# uwb.net
KiCad netlist of a schematic drawn in EAGLE
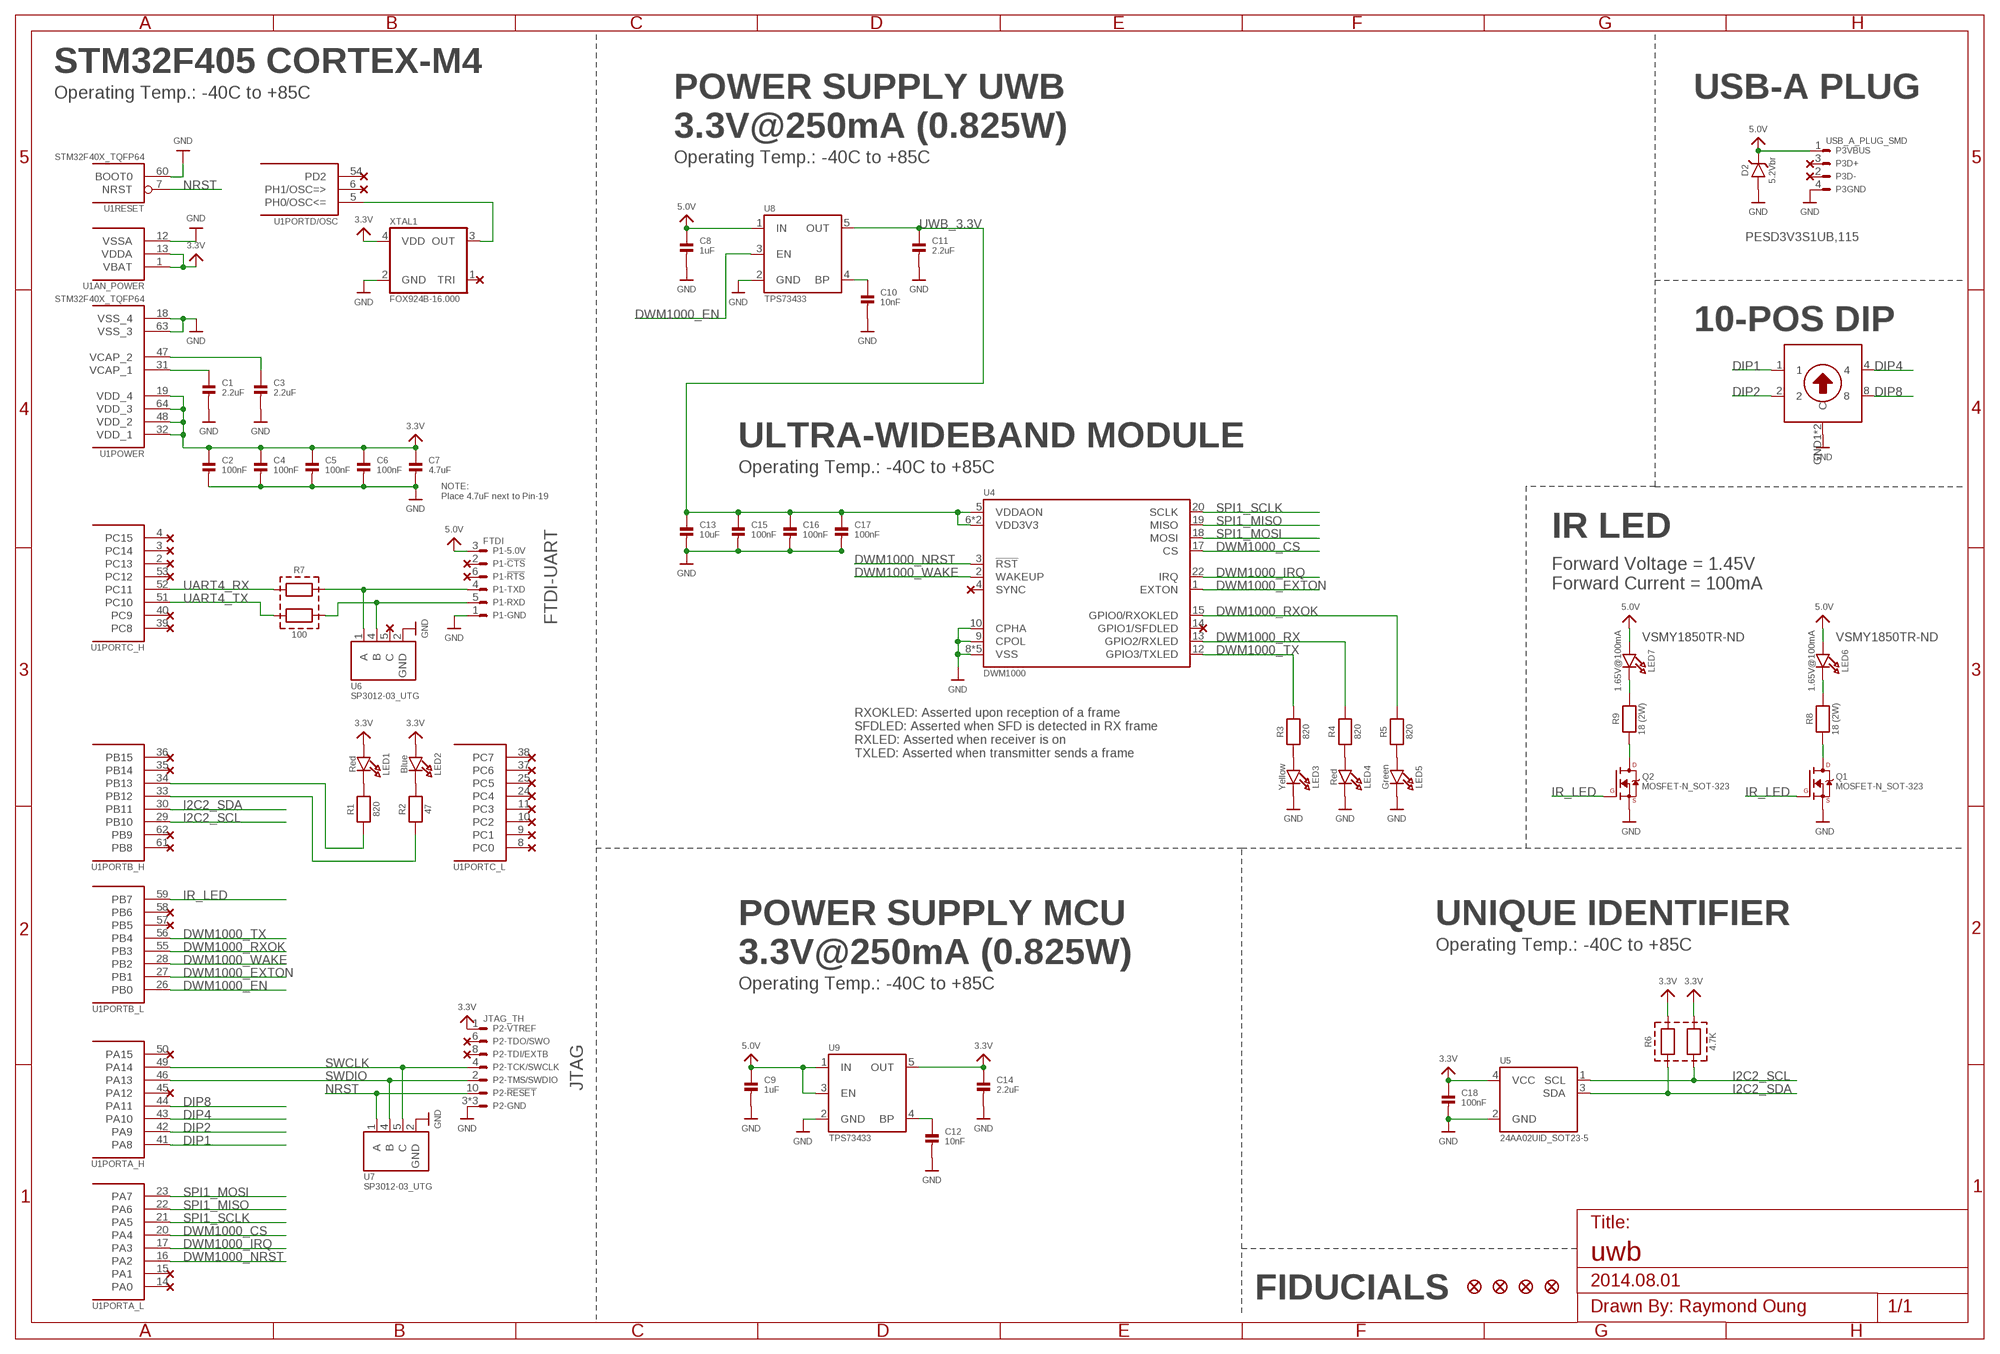
[diagram p0: schematic, sheet 1]

(export (version "E")
  (design (tool "Eeschema 10.0.6"))
  (components
    (comp (ref "C1")
      (value "2.2uF")
      (footprint "eagle-import:0402")
      (libsource (lib "eagle-import") (part "CAP_CERAMIC0402"))
    )
    (comp (ref "C2")
      (value "100nF")
      (footprint "eagle-import:0402")
      (libsource (lib "eagle-import") (part "CAP_CERAMIC0402"))
    )
    (comp (ref "C3")
      (value "2.2uF")
      (footprint "eagle-import:0402")
      (libsource (lib "eagle-import") (part "CAP_CERAMIC0402"))
    )
    (comp (ref "C4")
      (value "100nF")
      (footprint "eagle-import:0402")
      (libsource (lib "eagle-import") (part "CAP_CERAMIC0402"))
    )
    (comp (ref "C5")
      (value "100nF")
      (footprint "eagle-import:0402")
      (libsource (lib "eagle-import") (part "CAP_CERAMIC0402"))
    )
    (comp (ref "C6")
      (value "100nF")
      (footprint "eagle-import:0402")
      (libsource (lib "eagle-import") (part "CAP_CERAMIC0402"))
    )
    (comp (ref "C7")
      (value "4.7uF")
      (footprint "eagle-import:0402")
      (libsource (lib "eagle-import") (part "CAP_CERAMIC0402"))
    )
    (comp (ref "C8")
      (value "1uF")
      (footprint "eagle-import:0402")
      (libsource (lib "eagle-import") (part "CAP_CERAMIC0402"))
    )
    (comp (ref "C9")
      (value "1uF")
      (footprint "eagle-import:0402")
      (libsource (lib "eagle-import") (part "CAP_CERAMIC0402"))
    )
    (comp (ref "C10")
      (value "10nF")
      (footprint "eagle-import:0402")
      (libsource (lib "eagle-import") (part "CAP_CERAMIC0402"))
    )
    (comp (ref "C11")
      (value "2.2uF")
      (footprint "eagle-import:0402")
      (libsource (lib "eagle-import") (part "CAP_CERAMIC0402"))
    )
    (comp (ref "C12")
      (value "10nF")
      (footprint "eagle-import:0402")
      (libsource (lib "eagle-import") (part "CAP_CERAMIC0402"))
    )
    (comp (ref "C13")
      (value "10uF")
      (footprint "eagle-import:0603")
      (libsource (lib "eagle-import") (part "CAP_CERAMIC0603"))
    )
    (comp (ref "C14")
      (value "2.2uF")
      (footprint "eagle-import:0402")
      (libsource (lib "eagle-import") (part "CAP_CERAMIC0402"))
    )
    (comp (ref "C15")
      (value "100nF")
      (footprint "eagle-import:0402")
      (libsource (lib "eagle-import") (part "CAP_CERAMIC0402"))
    )
    (comp (ref "C16")
      (value "100nF")
      (footprint "eagle-import:0402")
      (libsource (lib "eagle-import") (part "CAP_CERAMIC0402"))
    )
    (comp (ref "C17")
      (value "100nF")
      (footprint "eagle-import:0402")
      (libsource (lib "eagle-import") (part "CAP_CERAMIC0402"))
    )
    (comp (ref "C18")
      (value "100nF")
      (footprint "eagle-import:0402")
      (libsource (lib "eagle-import") (part "CAP_CERAMIC0402"))
    )
    (comp (ref "D2")
      (value "5.2Vbr")
      (footprint "eagle-import:SOD-523")
      (libsource (lib "eagle-import") (part "DIODE_ZENER_SOD523"))
    )
    (comp (ref "LED1")
      (value "Red")
      (footprint "eagle-import:CHIPLED_0603")
      (libsource (lib "eagle-import") (part "LED_0603"))
    )
    (comp (ref "LED2")
      (value "Blue")
      (footprint "eagle-import:CHIPLED_0603")
      (libsource (lib "eagle-import") (part "LED_0603"))
    )
    (comp (ref "LED3")
      (value "Yellow")
      (footprint "eagle-import:CHIPLED_0603")
      (libsource (lib "eagle-import") (part "LED_0603"))
    )
    (comp (ref "LED4")
      (value "Red")
      (footprint "eagle-import:CHIPLED_0603")
      (libsource (lib "eagle-import") (part "LED_0603"))
    )
    (comp (ref "LED5")
      (value "Green")
      (footprint "eagle-import:CHIPLED_0603")
      (libsource (lib "eagle-import") (part "LED_0603"))
    )
    (comp (ref "LED6")
      (value "1.65V@100mA")
      (footprint "eagle-import:CHIPLED_0805")
      (libsource (lib "eagle-import") (part "LED_0805"))
    )
    (comp (ref "LED7")
      (value "1.65V@100mA")
      (footprint "eagle-import:CHIPLED_0805")
      (libsource (lib "eagle-import") (part "LED_0805"))
    )
    (comp (ref "P1")
      (value "FTDI")
      (footprint "eagle-import:1X06_LOCK")
      (libsource (lib "eagle-import") (part "FTDI"))
    )
    (comp (ref "P2")
      (value "JTAG_TH")
      (footprint "eagle-import:FTSH-105-01-XXX-DV")
      (libsource (lib "eagle-import") (part "JTAG_TH"))
    )
    (comp (ref "P3")
      (value "USB_A_PLUG_SMD")
      (footprint "eagle-import:USB-A_SMD")
      (libsource (lib "eagle-import") (part "USB_A_PLUG_SMD"))
    )
    (comp (ref "P4")
      (value "DIP10_SH-7000B")
      (footprint "eagle-import:SH-7000B")
      (libsource (lib "eagle-import") (part "DIP10_SH-7000B"))
    )
    (comp (ref "Q1")
      (value "MOSFET-N_SOT-323")
      (footprint "eagle-import:SOT323")
      (libsource (lib "eagle-import") (part "MOSFET-N_SOT-323"))
    )
    (comp (ref "Q2")
      (value "MOSFET-N_SOT-323")
      (footprint "eagle-import:SOT323")
      (libsource (lib "eagle-import") (part "MOSFET-N_SOT-323"))
    )
    (comp (ref "R1")
      (value "820")
      (footprint "eagle-import:0402")
      (libsource (lib "eagle-import") (part "RESISTOR0402"))
    )
    (comp (ref "R2")
      (value "47")
      (footprint "eagle-import:0402")
      (libsource (lib "eagle-import") (part "RESISTOR0402"))
    )
    (comp (ref "R3")
      (value "820")
      (footprint "eagle-import:0402")
      (libsource (lib "eagle-import") (part "RESISTOR0402"))
    )
    (comp (ref "R4")
      (value "820")
      (footprint "eagle-import:0402")
      (libsource (lib "eagle-import") (part "RESISTOR0402"))
    )
    (comp (ref "R5")
      (value "820")
      (footprint "eagle-import:0402")
      (libsource (lib "eagle-import") (part "RESISTOR0402"))
    )
    (comp (ref "R6")
      (value "4.7K")
      (footprint "eagle-import:EXBV4V")
      (libsource (lib "eagle-import") (part "RESISTOR2_0603X2"))
    )
    (comp (ref "R7")
      (value "100")
      (footprint "eagle-import:EXBV4V")
      (libsource (lib "eagle-import") (part "RESISTOR2_0603X2"))
    )
    (comp (ref "R8")
      (value "18 (2W)")
      (footprint "eagle-import:2512")
      (libsource (lib "eagle-import") (part "RESISTOR2512"))
    )
    (comp (ref "R9")
      (value "18 (2W)")
      (footprint "eagle-import:2512")
      (libsource (lib "eagle-import") (part "RESISTOR2512"))
    )
    (comp (ref "REF1")
      (value "FIDUCIAL1X2.5")
      (footprint "eagle-import:POINT-1MM")
      (libsource (lib "eagle-import") (part "FIDUCIAL1X2.5"))
    )
    (comp (ref "REF2")
      (value "FIDUCIAL1X2.5")
      (footprint "eagle-import:POINT-1MM")
      (libsource (lib "eagle-import") (part "FIDUCIAL1X2.5"))
    )
    (comp (ref "REF3")
      (value "FIDUCIAL1X2.5")
      (footprint "eagle-import:POINT-1MM")
      (libsource (lib "eagle-import") (part "FIDUCIAL1X2.5"))
    )
    (comp (ref "REF4")
      (value "FIDUCIAL1X2.5")
      (footprint "eagle-import:POINT-1MM")
      (libsource (lib "eagle-import") (part "FIDUCIAL1X2.5"))
    )
    (comp (ref "U1")
      (value "STM32F40X_TQFP64")
      (footprint "eagle-import:TQFP64")
      (libsource (lib "eagle-import") (part "STM32F40X_TQFP64"))
    )
    (comp (ref "U4")
      (value "DWM1000")
      (footprint "eagle-import:DWM1000")
      (libsource (lib "eagle-import") (part "DWM1000"))
    )
    (comp (ref "U5")
      (value "24AA02UID_SOT23-5")
      (footprint "eagle-import:SOT23-5")
      (libsource (lib "eagle-import") (part "24AA02UID_SOT23-5"))
    )
    (comp (ref "U6")
      (value "SP3012-03_UTG")
      (footprint "eagle-import:UDFN06")
      (libsource (lib "eagle-import") (part "SP3012-03_UTG"))
    )
    (comp (ref "U7")
      (value "SP3012-03_UTG")
      (footprint "eagle-import:UDFN06")
      (libsource (lib "eagle-import") (part "SP3012-03_UTG"))
    )
    (comp (ref "U8")
      (value "TPS73433")
      (footprint "eagle-import:SOT23-5")
      (libsource (lib "eagle-import") (part "TPS73433"))
    )
    (comp (ref "U9")
      (value "TPS73433")
      (footprint "eagle-import:SOT23-5")
      (libsource (lib "eagle-import") (part "TPS73433"))
    )
    (comp (ref "XTAL1")
      (value "FOX924B-16.000")
      (footprint "eagle-import:OSCILLATOR-5.0X3.2A")
      (libsource (lib "eagle-import") (part "TCXO_5.0X3.2A"))
    )
  )
  (nets
    (net (code "1") (name "/DIP1") (class "Default")
      (node (ref "P4") (pin "1") (pinfunction "1_1") (pintype "bidirectional"))
      (node (ref "U1") (pin "41") (pinfunction "PA8_41") (pintype "bidirectional"))
    )
    (net (code "2") (name "/DIP2") (class "Default")
      (node (ref "P4") (pin "2") (pinfunction "2_2") (pintype "bidirectional"))
      (node (ref "U1") (pin "42") (pinfunction "PA9_42") (pintype "bidirectional"))
    )
    (net (code "3") (name "/DIP4") (class "Default")
      (node (ref "P4") (pin "4") (pinfunction "4_4") (pintype "bidirectional"))
      (node (ref "U1") (pin "43") (pinfunction "PA10_43") (pintype "bidirectional"))
    )
    (net (code "4") (name "/DIP8") (class "Default")
      (node (ref "P4") (pin "8") (pinfunction "8_8") (pintype "bidirectional"))
      (node (ref "U1") (pin "44") (pinfunction "PA11_44") (pintype "bidirectional"))
    )
    (net (code "5") (name "/DWM1000_CS") (class "Default")
      (node (ref "U1") (pin "20") (pinfunction "PA4_20") (pintype "bidirectional"))
      (node (ref "U4") (pin "17") (pinfunction "CS_17") (pintype "input"))
    )
    (net (code "6") (name "/DWM1000_EN") (class "Default")
      (node (ref "U1") (pin "26") (pinfunction "PB0_26") (pintype "bidirectional"))
      (node (ref "U8") (pin "3") (pinfunction "EN_3") (pintype "bidirectional"))
    )
    (net (code "7") (name "/DWM1000_EXTON") (class "Default")
      (node (ref "U1") (pin "27") (pinfunction "PB1_27") (pintype "bidirectional"))
      (node (ref "U4") (pin "1") (pinfunction "EXTON_1") (pintype "output"))
    )
    (net (code "8") (name "/DWM1000_IRQ") (class "Default")
      (node (ref "U1") (pin "17") (pinfunction "PA3_17") (pintype "bidirectional"))
      (node (ref "U4") (pin "22") (pinfunction "IRQ_22") (pintype "output"))
    )
    (net (code "9") (name "/DWM1000_NRST") (class "Default")
      (node (ref "U1") (pin "16") (pinfunction "PA2_16") (pintype "bidirectional"))
      (node (ref "U4") (pin "3") (pinfunction "~{RST}_3") (pintype "bidirectional"))
    )
    (net (code "10") (name "/DWM1000_RX") (class "Default")
      (node (ref "R4") (pin "2") (pinfunction "2_2") (pintype "passive"))
      (node (ref "U4") (pin "13") (pinfunction "GPIO2/RXLED_13") (pintype "bidirectional"))
    )
    (net (code "11") (name "/DWM1000_RXOK") (class "Default")
      (node (ref "R5") (pin "2") (pinfunction "2_2") (pintype "passive"))
      (node (ref "U1") (pin "55") (pinfunction "PB3_55") (pintype "bidirectional"))
      (node (ref "U4") (pin "15") (pinfunction "GPIO0/RXOKLED_15") (pintype "bidirectional"))
    )
    (net (code "12") (name "/DWM1000_TX") (class "Default")
      (node (ref "R3") (pin "2") (pinfunction "2_2") (pintype "passive"))
      (node (ref "U1") (pin "56") (pinfunction "PB4_56") (pintype "bidirectional"))
      (node (ref "U4") (pin "12") (pinfunction "GPIO3/TXLED_12") (pintype "bidirectional"))
    )
    (net (code "13") (name "/DWM1000_WAKE") (class "Default")
      (node (ref "U1") (pin "28") (pinfunction "PB2_28") (pintype "bidirectional"))
      (node (ref "U4") (pin "2") (pinfunction "WAKEUP_2") (pintype "input"))
    )
    (net (code "14") (name "/I2C2_SCL") (class "Default")
      (node (ref "R6") (pin "2") (pinfunction "2_2") (pintype "passive"))
      (node (ref "U1") (pin "29") (pinfunction "PB10_29") (pintype "bidirectional"))
      (node (ref "U5") (pin "1") (pinfunction "SCL_1") (pintype "bidirectional"))
    )
    (net (code "15") (name "/I2C2_SDA") (class "Default")
      (node (ref "R6") (pin "1") (pinfunction "1_1") (pintype "passive"))
      (node (ref "U1") (pin "30") (pinfunction "PB11_30") (pintype "bidirectional"))
      (node (ref "U5") (pin "3") (pinfunction "SDA_3") (pintype "bidirectional"))
    )
    (net (code "16") (name "/IR_LED") (class "Default")
      (node (ref "Q1") (pin "1") (pinfunction "G_1") (pintype "bidirectional"))
      (node (ref "Q2") (pin "1") (pinfunction "G_1") (pintype "bidirectional"))
      (node (ref "U1") (pin "59") (pinfunction "PB7_59") (pintype "bidirectional"))
    )
    (net (code "17") (name "/NRST") (class "Default")
      (node (ref "P2") (pin "10") (pinfunction "S_10") (pintype "passive"))
      (node (ref "U1") (pin "7") (pinfunction "NRST_7") (pintype "input"))
      (node (ref "U7") (pin "1") (pinfunction "A_1") (pintype "bidirectional"))
    )
    (net (code "18") (name "/SPI1_MISO") (class "Default")
      (node (ref "U1") (pin "22") (pinfunction "PA6_22") (pintype "bidirectional"))
      (node (ref "U4") (pin "19") (pinfunction "MISO_19") (pintype "output"))
    )
    (net (code "19") (name "/SPI1_MOSI") (class "Default")
      (node (ref "U1") (pin "23") (pinfunction "PA7_23") (pintype "bidirectional"))
      (node (ref "U4") (pin "18") (pinfunction "MOSI_18") (pintype "input"))
    )
    (net (code "20") (name "/SPI1_SCLK") (class "Default")
      (node (ref "U1") (pin "21") (pinfunction "PA5_21") (pintype "bidirectional"))
      (node (ref "U4") (pin "20") (pinfunction "SCLK_20") (pintype "input"))
    )
    (net (code "21") (name "/SWCLK") (class "Default")
      (node (ref "P2") (pin "4") (pinfunction "S_4") (pintype "passive"))
      (node (ref "U1") (pin "49") (pinfunction "PA14_49") (pintype "bidirectional"))
      (node (ref "U7") (pin "5") (pinfunction "C_5") (pintype "bidirectional"))
    )
    (net (code "22") (name "/SWDIO") (class "Default")
      (node (ref "P2") (pin "2") (pinfunction "S_2") (pintype "passive"))
      (node (ref "U1") (pin "46") (pinfunction "PA13_46") (pintype "bidirectional"))
      (node (ref "U7") (pin "4") (pinfunction "B_4") (pintype "bidirectional"))
    )
    (net (code "23") (name "/UART4_RX") (class "Default")
      (node (ref "R7") (pin "1") (pinfunction "1_1") (pintype "passive"))
      (node (ref "U1") (pin "52") (pinfunction "PC11_52") (pintype "bidirectional"))
    )
    (net (code "24") (name "/UART4_TX") (class "Default")
      (node (ref "R7") (pin "2") (pinfunction "2_2") (pintype "passive"))
      (node (ref "U1") (pin "51") (pinfunction "PC10_51") (pintype "bidirectional"))
    )
    (net (code "25") (name "/UWB_3.3V") (class "Default")
      (node (ref "C11") (pin "1") (pinfunction "P$1_1") (pintype "passive"))
      (node (ref "C13") (pin "1") (pinfunction "P$1_1") (pintype "passive"))
      (node (ref "C15") (pin "1") (pinfunction "P$1_1") (pintype "passive"))
      (node (ref "C16") (pin "1") (pinfunction "P$1_1") (pintype "passive"))
      (node (ref "C17") (pin "1") (pinfunction "P$1_1") (pintype "passive"))
      (node (ref "U4") (pin "5") (pinfunction "VDDAON_5") (pintype "power_in"))
      (node (ref "U4") (pin "6") (pinfunction "VDD3V3_6") (pintype "power_in"))
      (node (ref "U4") (pin "7") (pinfunction "VDD3V3_7") (pintype "power_in"))
      (node (ref "U8") (pin "5") (pinfunction "OUT_5") (pintype "bidirectional"))
    )
    (net (code "26") (name "3.3V") (class "Default")
      (node (ref "C14") (pin "1") (pinfunction "P$1_1") (pintype "passive"))
      (node (ref "C18") (pin "1") (pinfunction "P$1_1") (pintype "passive"))
      (node (ref "C2") (pin "1") (pinfunction "P$1_1") (pintype "passive"))
      (node (ref "C4") (pin "1") (pinfunction "P$1_1") (pintype "passive"))
      (node (ref "C5") (pin "1") (pinfunction "P$1_1") (pintype "passive"))
      (node (ref "C6") (pin "1") (pinfunction "P$1_1") (pintype "passive"))
      (node (ref "C7") (pin "1") (pinfunction "P$1_1") (pintype "passive"))
      (node (ref "LED1") (pin "A") (pinfunction "A_A") (pintype "passive"))
      (node (ref "LED2") (pin "A") (pinfunction "A_A") (pintype "passive"))
      (node (ref "P2") (pin "1") (pinfunction "S_1") (pintype "passive"))
      (node (ref "R6") (pin "3") (pinfunction "3_3") (pintype "passive"))
      (node (ref "R6") (pin "4") (pinfunction "4_4") (pintype "passive"))
      (node (ref "U1") (pin "1") (pinfunction "VBAT_1") (pintype "power_in"))
      (node (ref "U1") (pin "13") (pinfunction "VDDA_13") (pintype "power_in"))
      (node (ref "U1") (pin "19") (pinfunction "VDD_4_19") (pintype "power_in"))
      (node (ref "U1") (pin "32") (pinfunction "VDD_1_32") (pintype "power_in"))
      (node (ref "U1") (pin "48") (pinfunction "VDD_2_48") (pintype "power_in"))
      (node (ref "U1") (pin "64") (pinfunction "VDD_3_64") (pintype "power_in"))
      (node (ref "U5") (pin "4") (pinfunction "VCC_4") (pintype "bidirectional"))
      (node (ref "U9") (pin "5") (pinfunction "OUT_5") (pintype "bidirectional"))
      (node (ref "XTAL1") (pin "4") (pinfunction "VDD_4") (pintype "bidirectional"))
    )
    (net (code "27") (name "5.0V") (class "Default")
      (node (ref "C8") (pin "1") (pinfunction "P$1_1") (pintype "passive"))
      (node (ref "C9") (pin "1") (pinfunction "P$1_1") (pintype "passive"))
      (node (ref "D2") (pin "K") (pinfunction "C_K") (pintype "passive"))
      (node (ref "LED6") (pin "A") (pinfunction "A_A") (pintype "passive"))
      (node (ref "LED7") (pin "A") (pinfunction "A_A") (pintype "passive"))
      (node (ref "P1") (pin "3") (pinfunction "S_3") (pintype "passive"))
      (node (ref "P3") (pin "1") (pinfunction "S_1") (pintype "passive"))
      (node (ref "U8") (pin "1") (pinfunction "IN_1") (pintype "bidirectional"))
      (node (ref "U9") (pin "1") (pinfunction "IN_1") (pintype "bidirectional"))
      (node (ref "U9") (pin "3") (pinfunction "EN_3") (pintype "bidirectional"))
    )
    (net (code "28") (name "GND") (class "Default")
      (node (ref "C1") (pin "2") (pinfunction "P$2_2") (pintype "passive"))
      (node (ref "C10") (pin "2") (pinfunction "P$2_2") (pintype "passive"))
      (node (ref "C11") (pin "2") (pinfunction "P$2_2") (pintype "passive"))
      (node (ref "C12") (pin "2") (pinfunction "P$2_2") (pintype "passive"))
      (node (ref "C13") (pin "2") (pinfunction "P$2_2") (pintype "passive"))
      (node (ref "C14") (pin "2") (pinfunction "P$2_2") (pintype "passive"))
      (node (ref "C15") (pin "2") (pinfunction "P$2_2") (pintype "passive"))
      (node (ref "C16") (pin "2") (pinfunction "P$2_2") (pintype "passive"))
      (node (ref "C17") (pin "2") (pinfunction "P$2_2") (pintype "passive"))
      (node (ref "C18") (pin "2") (pinfunction "P$2_2") (pintype "passive"))
      (node (ref "C2") (pin "2") (pinfunction "P$2_2") (pintype "passive"))
      (node (ref "C3") (pin "2") (pinfunction "P$2_2") (pintype "passive"))
      (node (ref "C4") (pin "2") (pinfunction "P$2_2") (pintype "passive"))
      (node (ref "C5") (pin "2") (pinfunction "P$2_2") (pintype "passive"))
      (node (ref "C6") (pin "2") (pinfunction "P$2_2") (pintype "passive"))
      (node (ref "C7") (pin "2") (pinfunction "P$2_2") (pintype "passive"))
      (node (ref "C8") (pin "2") (pinfunction "P$2_2") (pintype "passive"))
      (node (ref "C9") (pin "2") (pinfunction "P$2_2") (pintype "passive"))
      (node (ref "D2") (pin "A") (pinfunction "A_A") (pintype "passive"))
      (node (ref "LED3") (pin "C") (pinfunction "C_C") (pintype "passive"))
      (node (ref "LED4") (pin "C") (pinfunction "C_C") (pintype "passive"))
      (node (ref "LED5") (pin "C") (pinfunction "C_C") (pintype "passive"))
      (node (ref "P1") (pin "1") (pinfunction "S_1") (pintype "passive"))
      (node (ref "P2") (pin "3") (pinfunction "S_3") (pintype "passive"))
      (node (ref "P2") (pin "5") (pinfunction "S_5") (pintype "passive"))
      (node (ref "P2") (pin "9") (pinfunction "S_9") (pintype "passive"))
      (node (ref "P3") (pin "4") (pinfunction "S_4") (pintype "passive"))
      (node (ref "P4") (pin "GND1") (pinfunction "C_GND1") (pintype "bidirectional"))
      (node (ref "P4") (pin "GND2") (pinfunction "C_GND2") (pintype "bidirectional"))
      (node (ref "Q1") (pin "2") (pinfunction "S_2") (pintype "bidirectional"))
      (node (ref "Q2") (pin "2") (pinfunction "S_2") (pintype "bidirectional"))
      (node (ref "U1") (pin "12") (pinfunction "VSSA_12") (pintype "power_in"))
      (node (ref "U1") (pin "18") (pinfunction "VSS_4_18") (pintype "power_in"))
      (node (ref "U1") (pin "60") (pinfunction "BOOT0_60") (pintype "input"))
      (node (ref "U1") (pin "63") (pinfunction "VSS_3_63") (pintype "power_in"))
      (node (ref "U4") (pin "10") (pinfunction "CPHA_10") (pintype "bidirectional"))
      (node (ref "U4") (pin "16") (pinfunction "VSS_16") (pintype "bidirectional"))
      (node (ref "U4") (pin "21") (pinfunction "VSS_21") (pintype "bidirectional"))
      (node (ref "U4") (pin "23") (pinfunction "VSS_23") (pintype "bidirectional"))
      (node (ref "U4") (pin "24") (pinfunction "VSS_24") (pintype "bidirectional"))
      (node (ref "U4") (pin "8") (pinfunction "VSS_8") (pintype "bidirectional"))
      (node (ref "U4") (pin "9") (pinfunction "CPOL_9") (pintype "bidirectional"))
      (node (ref "U5") (pin "2") (pinfunction "GND_2") (pintype "bidirectional"))
      (node (ref "U6") (pin "2") (pinfunction "GND_2") (pintype "power_in"))
      (node (ref "U7") (pin "2") (pinfunction "GND_2") (pintype "power_in"))
      (node (ref "U8") (pin "2") (pinfunction "GND_2") (pintype "bidirectional"))
      (node (ref "U9") (pin "2") (pinfunction "GND_2") (pintype "bidirectional"))
      (node (ref "XTAL1") (pin "2") (pinfunction "GND_2") (pintype "bidirectional"))
    )
    (net (code "29") (name "Net-(C1-P$1)") (class "Default")
      (node (ref "C1") (pin "1") (pinfunction "P$1_1") (pintype "passive"))
      (node (ref "U1") (pin "31") (pinfunction "VCAP_1_31") (pintype "power_in"))
    )
    (net (code "30") (name "Net-(C3-P$1)") (class "Default")
      (node (ref "C3") (pin "1") (pinfunction "P$1_1") (pintype "passive"))
      (node (ref "U1") (pin "47") (pinfunction "VCAP_2_47") (pintype "power_in"))
    )
    (net (code "31") (name "Net-(C10-P$1)") (class "Default")
      (node (ref "C10") (pin "1") (pinfunction "P$1_1") (pintype "passive"))
      (node (ref "U8") (pin "4") (pinfunction "BP_4") (pintype "bidirectional"))
    )
    (net (code "32") (name "Net-(C12-P$1)") (class "Default")
      (node (ref "C12") (pin "1") (pinfunction "P$1_1") (pintype "passive"))
      (node (ref "U9") (pin "4") (pinfunction "BP_4") (pintype "bidirectional"))
    )
    (net (code "33") (name "Net-(LED1-PadC)") (class "Default")
      (node (ref "LED1") (pin "C") (pinfunction "C_C") (pintype "passive"))
      (node (ref "R1") (pin "2") (pinfunction "2_2") (pintype "passive"))
    )
    (net (code "34") (name "Net-(LED2-PadC)") (class "Default")
      (node (ref "LED2") (pin "C") (pinfunction "C_C") (pintype "passive"))
      (node (ref "R2") (pin "2") (pinfunction "2_2") (pintype "passive"))
    )
    (net (code "35") (name "Net-(LED3-PadA)") (class "Default")
      (node (ref "LED3") (pin "A") (pinfunction "A_A") (pintype "passive"))
      (node (ref "R3") (pin "1") (pinfunction "1_1") (pintype "passive"))
    )
    (net (code "36") (name "Net-(LED4-PadA)") (class "Default")
      (node (ref "LED4") (pin "A") (pinfunction "A_A") (pintype "passive"))
      (node (ref "R4") (pin "1") (pinfunction "1_1") (pintype "passive"))
    )
    (net (code "37") (name "Net-(LED5-PadA)") (class "Default")
      (node (ref "LED5") (pin "A") (pinfunction "A_A") (pintype "passive"))
      (node (ref "R5") (pin "1") (pinfunction "1_1") (pintype "passive"))
    )
    (net (code "38") (name "Net-(LED6-PadC)") (class "Default")
      (node (ref "LED6") (pin "C") (pinfunction "C_C") (pintype "passive"))
      (node (ref "R8") (pin "2") (pinfunction "2_2") (pintype "passive"))
    )
    (net (code "39") (name "Net-(LED7-PadC)") (class "Default")
      (node (ref "LED7") (pin "C") (pinfunction "C_C") (pintype "passive"))
      (node (ref "R9") (pin "2") (pinfunction "2_2") (pintype "passive"))
    )
    (net (code "40") (name "Net-(P1E-S)") (class "Default")
      (node (ref "P1") (pin "5") (pinfunction "S_5") (pintype "passive"))
      (node (ref "R7") (pin "3") (pinfunction "3_3") (pintype "passive"))
      (node (ref "U6") (pin "4") (pinfunction "B_4") (pintype "bidirectional"))
    )
    (net (code "41") (name "Net-(P1F-S)") (class "Default")
      (node (ref "P1") (pin "4") (pinfunction "S_4") (pintype "passive"))
      (node (ref "R7") (pin "4") (pinfunction "4_4") (pintype "passive"))
      (node (ref "U6") (pin "1") (pinfunction "A_1") (pintype "bidirectional"))
    )
    (net (code "42") (name "Net-(Q1-D)") (class "Default")
      (node (ref "Q1") (pin "3") (pinfunction "D_3") (pintype "bidirectional"))
      (node (ref "R8") (pin "1") (pinfunction "1_1") (pintype "passive"))
    )
    (net (code "43") (name "Net-(Q2-D)") (class "Default")
      (node (ref "Q2") (pin "3") (pinfunction "D_3") (pintype "bidirectional"))
      (node (ref "R9") (pin "1") (pinfunction "1_1") (pintype "passive"))
    )
    (net (code "44") (name "Net-(U1D-PB12)") (class "Default")
      (node (ref "R2") (pin "1") (pinfunction "1_1") (pintype "passive"))
      (node (ref "U1") (pin "33") (pinfunction "PB12_33") (pintype "bidirectional"))
    )
    (net (code "45") (name "Net-(U1D-PB13)") (class "Default")
      (node (ref "R1") (pin "1") (pinfunction "1_1") (pintype "passive"))
      (node (ref "U1") (pin "34") (pinfunction "PB13_34") (pintype "bidirectional"))
    )
    (net (code "46") (name "Net-(U1H-PH0{slash}OSC<=)") (class "Default")
      (node (ref "U1") (pin "5") (pinfunction "PH0/OSC<=_5") (pintype "bidirectional"))
      (node (ref "XTAL1") (pin "3") (pinfunction "OUT_3") (pintype "bidirectional"))
    )
    (net (code "47") (name "unconnected-(P1A-S-Pad2)") (class "Default")
      (node (ref "P1") (pin "2") (pinfunction "S_2") (pintype "passive"))
    )
    (net (code "48") (name "unconnected-(P1B-S-Pad6)") (class "Default")
      (node (ref "P1") (pin "6") (pinfunction "S_6") (pintype "passive"))
    )
    (net (code "49") (name "unconnected-(P2D-S-Pad8)") (class "Default")
      (node (ref "P2") (pin "8") (pinfunction "S_8") (pintype "passive"))
    )
    (net (code "50") (name "unconnected-(P2E-S-Pad6)") (class "Default")
      (node (ref "P2") (pin "6") (pinfunction "S_6") (pintype "passive"))
    )
    (net (code "51") (name "unconnected-(P3A-S-Pad3)") (class "Default")
      (node (ref "P3") (pin "3") (pinfunction "S_3") (pintype "passive"))
    )
    (net (code "52") (name "unconnected-(P3B-S-Pad2)") (class "Default")
      (node (ref "P3") (pin "2") (pinfunction "S_2") (pintype "passive"))
    )
    (net (code "53") (name "unconnected-(U1B-PA12-Pad45)") (class "Default")
      (node (ref "U1") (pin "45") (pinfunction "PA12_45") (pintype "bidirectional"))
    )
    (net (code "54") (name "unconnected-(U1B-PA15-Pad50)") (class "Default")
      (node (ref "U1") (pin "50") (pinfunction "PA15_50") (pintype "bidirectional"))
    )
    (net (code "55") (name "unconnected-(U1C-PA0-Pad14)") (class "Default")
      (node (ref "U1") (pin "14") (pinfunction "PA0_14") (pintype "bidirectional"))
    )
    (net (code "56") (name "unconnected-(U1C-PA1-Pad15)") (class "Default")
      (node (ref "U1") (pin "15") (pinfunction "PA1_15") (pintype "bidirectional"))
    )
    (net (code "57") (name "unconnected-(U1D-PB8-Pad61)") (class "Default")
      (node (ref "U1") (pin "61") (pinfunction "PB8_61") (pintype "bidirectional"))
    )
    (net (code "58") (name "unconnected-(U1D-PB9-Pad62)") (class "Default")
      (node (ref "U1") (pin "62") (pinfunction "PB9_62") (pintype "bidirectional"))
    )
    (net (code "59") (name "unconnected-(U1D-PB14-Pad35)") (class "Default")
      (node (ref "U1") (pin "35") (pinfunction "PB14_35") (pintype "bidirectional"))
    )
    (net (code "60") (name "unconnected-(U1D-PB15-Pad36)") (class "Default")
      (node (ref "U1") (pin "36") (pinfunction "PB15_36") (pintype "bidirectional"))
    )
    (net (code "61") (name "unconnected-(U1E-PB5-Pad57)") (class "Default")
      (node (ref "U1") (pin "57") (pinfunction "PB5_57") (pintype "bidirectional"))
    )
    (net (code "62") (name "unconnected-(U1E-PB6-Pad58)") (class "Default")
      (node (ref "U1") (pin "58") (pinfunction "PB6_58") (pintype "bidirectional"))
    )
    (net (code "63") (name "unconnected-(U1F-PC8-Pad39)") (class "Default")
      (node (ref "U1") (pin "39") (pinfunction "PC8_39") (pintype "bidirectional"))
    )
    (net (code "64") (name "unconnected-(U1F-PC9-Pad40)") (class "Default")
      (node (ref "U1") (pin "40") (pinfunction "PC9_40") (pintype "bidirectional"))
    )
    (net (code "65") (name "unconnected-(U1F-PC12-Pad53)") (class "Default")
      (node (ref "U1") (pin "53") (pinfunction "PC12_53") (pintype "bidirectional"))
    )
    (net (code "66") (name "unconnected-(U1F-PC13-Pad2)") (class "Default")
      (node (ref "U1") (pin "2") (pinfunction "PC13_2") (pintype "bidirectional"))
    )
    (net (code "67") (name "unconnected-(U1F-PC14-Pad3)") (class "Default")
      (node (ref "U1") (pin "3") (pinfunction "PC14_3") (pintype "bidirectional"))
    )
    (net (code "68") (name "unconnected-(U1F-PC15-Pad4)") (class "Default")
      (node (ref "U1") (pin "4") (pinfunction "PC15_4") (pintype "bidirectional"))
    )
    (net (code "69") (name "unconnected-(U1G-PC0-Pad8)") (class "Default")
      (node (ref "U1") (pin "8") (pinfunction "PC0_8") (pintype "bidirectional"))
    )
    (net (code "70") (name "unconnected-(U1G-PC1-Pad9)") (class "Default")
      (node (ref "U1") (pin "9") (pinfunction "PC1_9") (pintype "bidirectional"))
    )
    (net (code "71") (name "unconnected-(U1G-PC2-Pad10)") (class "Default")
      (node (ref "U1") (pin "10") (pinfunction "PC2_10") (pintype "bidirectional"))
    )
    (net (code "72") (name "unconnected-(U1G-PC3-Pad11)") (class "Default")
      (node (ref "U1") (pin "11") (pinfunction "PC3_11") (pintype "bidirectional"))
    )
    (net (code "73") (name "unconnected-(U1G-PC4-Pad24)") (class "Default")
      (node (ref "U1") (pin "24") (pinfunction "PC4_24") (pintype "bidirectional"))
    )
    (net (code "74") (name "unconnected-(U1G-PC5-Pad25)") (class "Default")
      (node (ref "U1") (pin "25") (pinfunction "PC5_25") (pintype "bidirectional"))
    )
    (net (code "75") (name "unconnected-(U1G-PC6-Pad37)") (class "Default")
      (node (ref "U1") (pin "37") (pinfunction "PC6_37") (pintype "bidirectional"))
    )
    (net (code "76") (name "unconnected-(U1G-PC7-Pad38)") (class "Default")
      (node (ref "U1") (pin "38") (pinfunction "PC7_38") (pintype "bidirectional"))
    )
    (net (code "77") (name "unconnected-(U1H-PD2-Pad54)") (class "Default")
      (node (ref "U1") (pin "54") (pinfunction "PD2_54") (pintype "bidirectional"))
    )
    (net (code "78") (name "unconnected-(U1H-PH1{slash}OSC=>-Pad6)") (class "Default")
      (node (ref "U1") (pin "6") (pinfunction "PH1/OSC=>_6") (pintype "bidirectional"))
    )
    (net (code "79") (name "unconnected-(U4-GPIO1{slash}SFDLED-Pad14)") (class "Default")
      (node (ref "U4") (pin "14") (pinfunction "GPIO1/SFDLED_14") (pintype "bidirectional"))
    )
    (net (code "80") (name "unconnected-(U4-SYNC-Pad4)") (class "Default")
      (node (ref "U4") (pin "4") (pinfunction "SYNC_4") (pintype "input"))
    )
    (net (code "81") (name "unconnected-(U6-C-Pad5)") (class "Default")
      (node (ref "U6") (pin "5") (pinfunction "C_5") (pintype "bidirectional"))
    )
    (net (code "82") (name "unconnected-(XTAL1-TRI-Pad1)") (class "Default")
      (node (ref "XTAL1") (pin "1") (pinfunction "TRI_1") (pintype "bidirectional"))
    )
  )
)
